# STM32WB09.net
KiCad netlist of a schematic drawn in Altium Designer
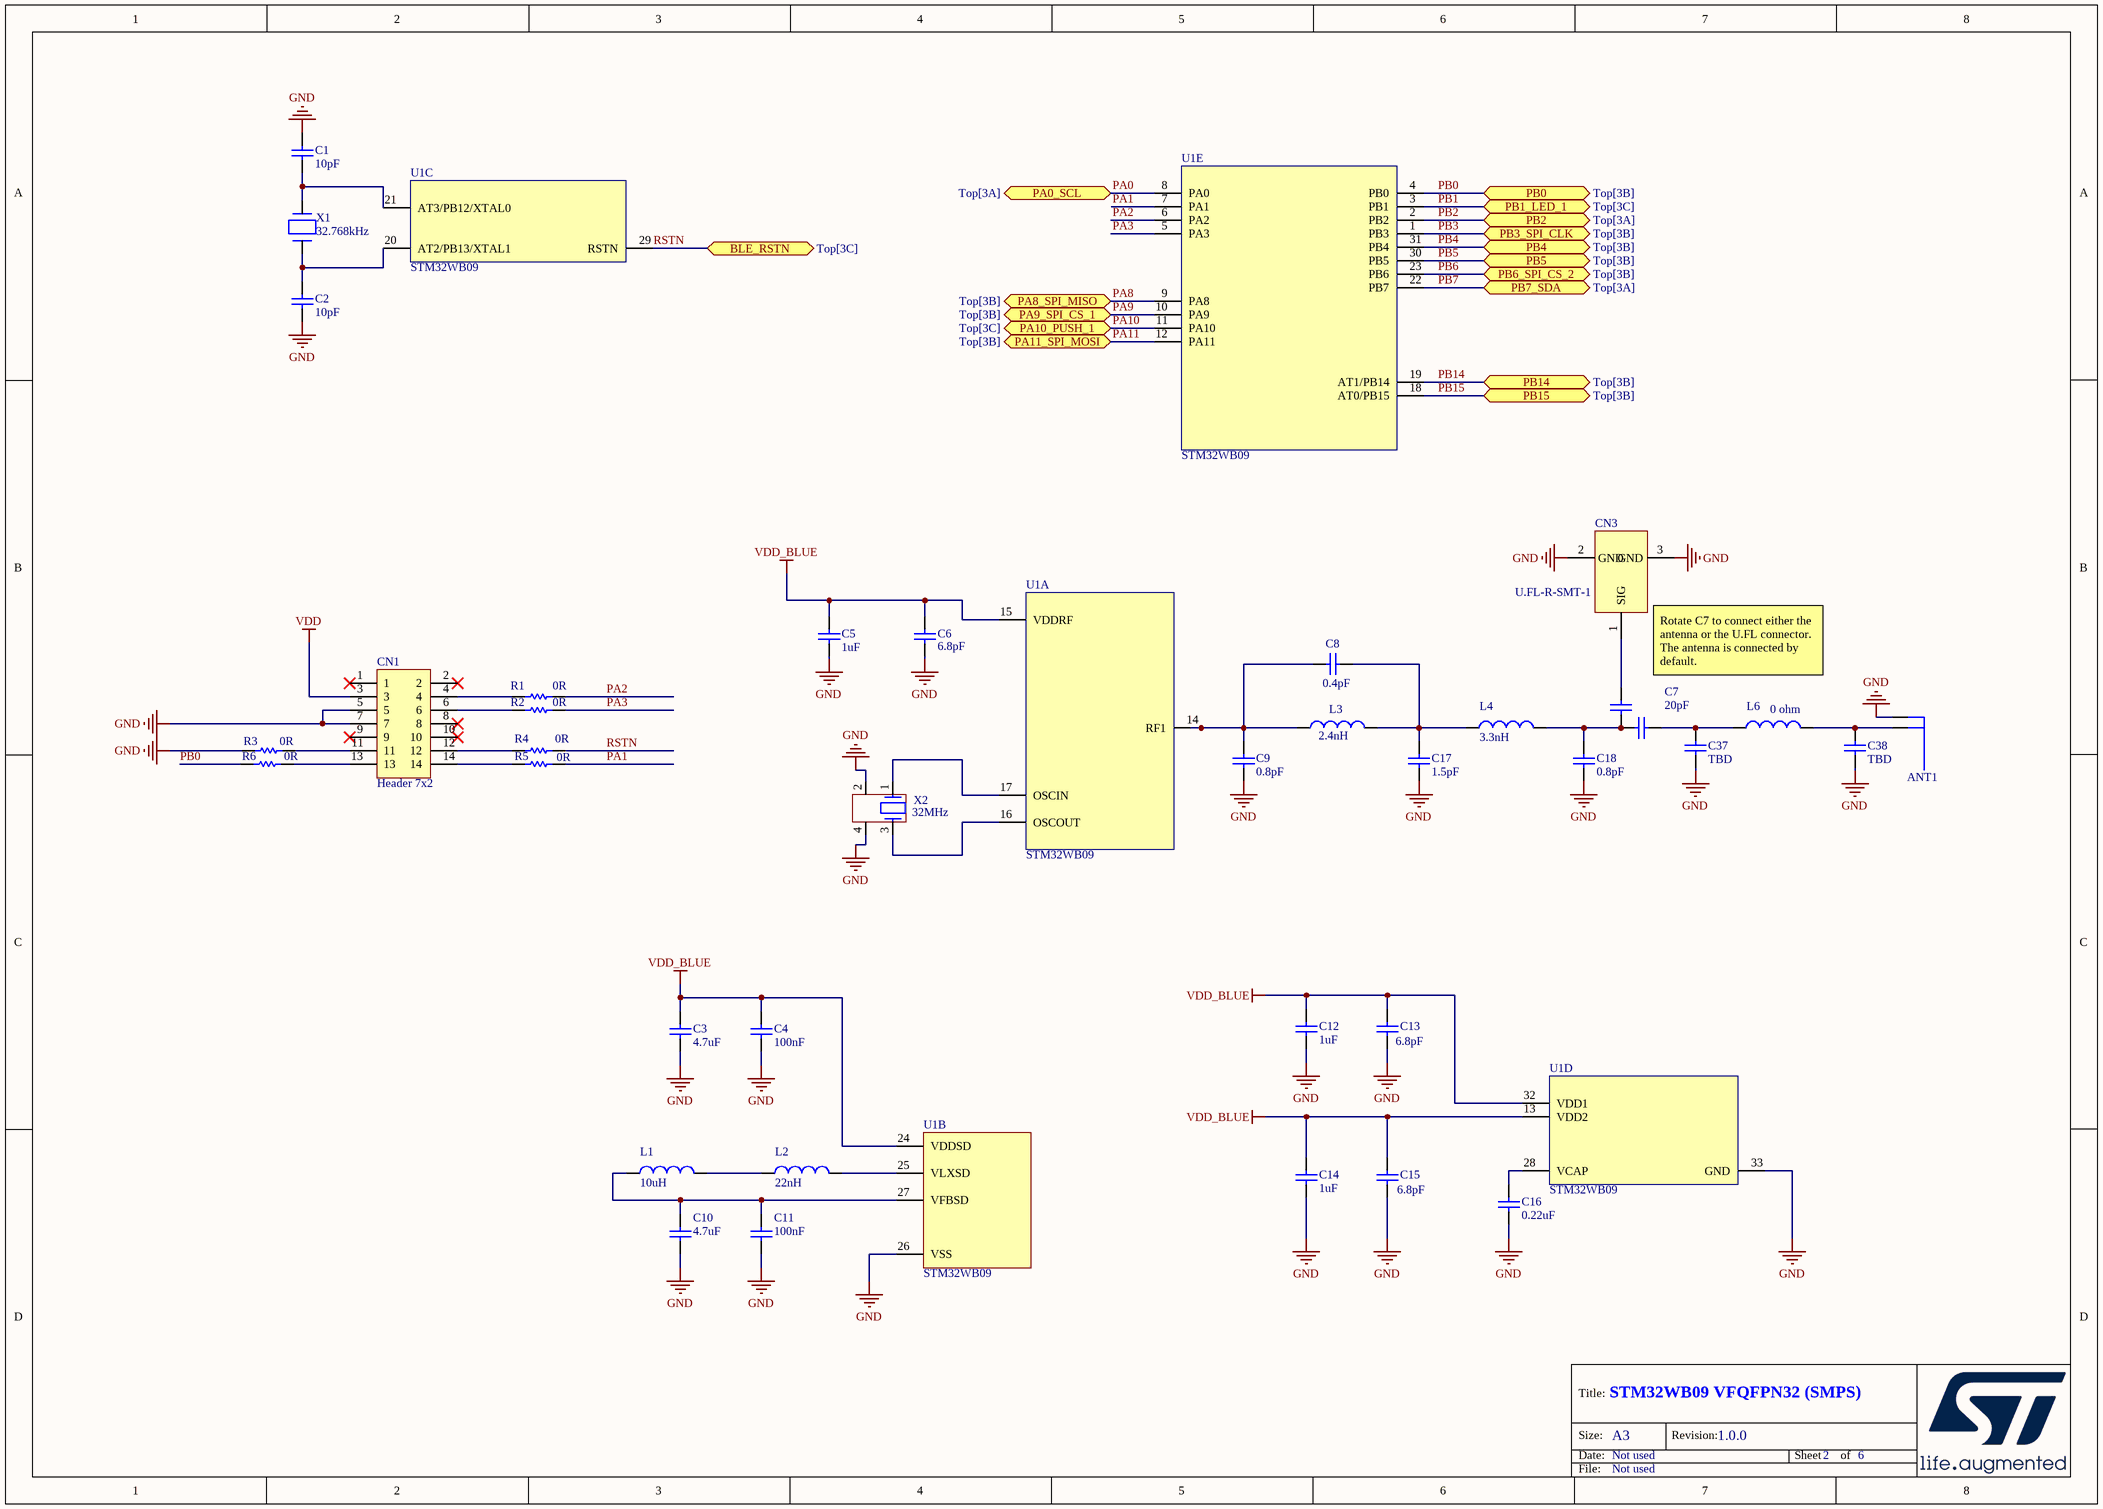
[diagram p0: STM32WB09.SchDoc]

(export (version "E")
  (design (tool "Eeschema 10.0.6"))
  (components
    (comp (ref "ANT1")
      (value "BLE_ANT")
      (footprint "ANTENNA_F")
      (description "2.4 GHz PIFA")
      (libsource (lib "STEVAL-ESLBLECB") (part "BLE_ANT"))
    )
    (comp (ref "C1")
      (value "10pF")
      (footprint "C0402")
      (description "Capacitor, MLCC, 10pF, 50V, NPO, +/-5%, 0402, T=0.5mm")
      (fields (field (name "INTERNAL_PART_NUMBER") "MCD-00015") (field (name "MANUFACTURER") "YAGEO"))
      (libsource (lib "MCD_PARTS_database") (part "Capacitor"))
    )
    (comp (ref "C2")
      (value "10pF")
      (footprint "C0402")
      (description "Capacitor, MLCC, 10pF, 50V, NPO, +/-5%, 0402, T=0.5mm")
      (fields (field (name "INTERNAL_PART_NUMBER") "MCD-00015") (field (name "MANUFACTURER") "YAGEO"))
      (libsource (lib "MCD_PARTS_database") (part "Capacitor"))
    )
    (comp (ref "C3")
      (value "4.7uF")
      (footprint "C0402")
      (description "Capacitor, MLCC, 4.7uF, X5R, 10V, +/-20%, 0402, T=0.5mm")
      (fields (field (name "INTERNAL_PART_NUMBER") "MCD-03431") (field (name "MANUFACTURER") "MURATA"))
      (libsource (lib "MCD_PARTS_database") (part "Capacitor"))
    )
    (comp (ref "C4")
      (value "100nF")
      (footprint "C0201_H0P3")
      (description "Capacitor, MLCC,100nF, 10V, X5R, +/-10%, 0201, T=0.3mm")
      (fields (field (name "INTERNAL_PART_NUMBER") "MCD-01535") (field (name "MANUFACTURER") "MURATA"))
      (libsource (lib "MCD_PARTS_database") (part "Capacitor"))
    )
    (comp (ref "C5")
      (value "1uF")
      (footprint "C0402")
      (description "Capacitor, MLCC, 1uF, X7R, 6.3V,+/- 10%, 0402, T=0.5mm")
      (fields (field (name "INTERNAL_PART_NUMBER") "MCD-03432") (field (name "MANUFACTURER") "MURATA"))
      (libsource (lib "MCD_PARTS_database") (part "Capacitor"))
    )
    (comp (ref "C6")
      (value "6.8pF")
      (footprint "C0201_H0P3")
      (description "Cap Ceramic 6.8pF 25V C0G 0.25pF SMD 0201 125°C Paper T/R")
      (fields
        (field (name "MANUFACTURER") "Murata")
        (field (name "MANUFACTURER PART NUMBER") "GJM0335C1E6R8CB01D")
      )
      (libsource (lib "MCD_PARTS_database") (part "Capacitor"))
    )
    (comp (ref "C7")
      (value "20pF")
      (footprint "SMD 0201 DEV")
      (description "Cap Ceramic 20pF 25V C0G 2% Pad SMD 0201 125C T/R")
      (fields
        (field (name "MANUFACTURER") "Murata")
        (field (name "MANUFACTURER PART NUMBER") "GJM0335C1E200GB01D")
      )
      (libsource (lib "STEVAL-ESLBLECB") (part "C_0201_DEV"))
    )
    (comp (ref "C8")
      (value "0.4pF")
      (footprint "0_5p_capacitor_SMD_0201")
      (description "0201 0.4 pF 25 V ±0.05 pF Tolerance C0G SMT Multilayer Ceramic Capacitor")
      (fields
        (field (name "MANUFACTURER") "Murata")
        (field (name "MANUFACTURER PART NUMBER") "GJM0335C1ER40WB01D")
      )
      (libsource (lib "STEVAL-ESLBLECB") (part "MCD-02284_2"))
    )
    (comp (ref "C9")
      (value "0.8pF")
      (footprint "0_8p_capacitor_SMD_0201")
      (description "Multilayer Ceramic Capacitor, 0.8 pF, 25 V, ± 0.05pF, C0G (NP0), 0201 [0603 Metric]")
      (fields
        (field (name "MANUFACTURER") "Murata")
        (field (name "MANUFACTURER PART NUMBER") "GJM0335C1ER80WB01D")
      )
      (libsource (lib "STEVAL-ESLBLECB") (part "MCD-02284_1"))
    )
    (comp (ref "C10")
      (value "4.7uF")
      (footprint "C0402")
      (description "Capacitor, MLCC, 4.7uF, X5R, 10V, +/-20%, 0402, T=0.5mm")
      (fields (field (name "INTERNAL_PART_NUMBER") "MCD-03431") (field (name "MANUFACTURER") "MURATA"))
      (libsource (lib "MCD_PARTS_database") (part "Capacitor"))
    )
    (comp (ref "C11")
      (value "100nF")
      (footprint "C0402")
      (description "Capacitor, MLCC, 100nF, +/-10%, X7R, 25V, 0402, T=0.5mm")
      (fields (field (name "INTERNAL_PART_NUMBER") "MCD-03442") (field (name "MANUFACTURER") "MURATA"))
      (libsource (lib "MCD_PARTS_database") (part "Capacitor"))
    )
    (comp (ref "C12")
      (value "1uF")
      (footprint "C0402")
      (description "Capacitor, MLCC, 1uF, X7R, 6.3V,+/- 10%, 0402, T=0.5mm")
      (fields (field (name "INTERNAL_PART_NUMBER") "MCD-03432") (field (name "MANUFACTURER") "MURATA"))
      (libsource (lib "MCD_PARTS_database") (part "Capacitor"))
    )
    (comp (ref "C13")
      (value "6.8pF")
      (footprint "C0201_H0P3")
      (description "Cap Ceramic 6.8pF 25V C0G 0.25pF SMD 0201 125°C Paper T/R")
      (fields
        (field (name "MANUFACTURER") "Murata")
        (field (name "MANUFACTURER PART NUMBER") "GJM0335C1E6R8CB01D")
      )
      (libsource (lib "MCD_PARTS_database") (part "Capacitor"))
    )
    (comp (ref "C14")
      (value "1uF")
      (footprint "C0402")
      (description "Capacitor, MLCC, 1uF, X7R, 6.3V,+/- 10%, 0402, T=0.5mm")
      (fields (field (name "INTERNAL_PART_NUMBER") "MCD-03432") (field (name "MANUFACTURER") "MURATA"))
      (libsource (lib "MCD_PARTS_database") (part "Capacitor"))
    )
    (comp (ref "C15")
      (value "6.8pF")
      (footprint "C0201_H0P3")
      (description "Cap Ceramic 6.8pF 25V C0G 0.25pF SMD 0201 125°C Paper T/R")
      (fields
        (field (name "MANUFACTURER") "Murata")
        (field (name "MANUFACTURER PART NUMBER") "GJM0335C1E6R8CB01D")
      )
      (libsource (lib "MCD_PARTS_database") (part "Capacitor"))
    )
    (comp (ref "C16")
      (value "0.22uF")
      (footprint "C0402")
      (description "Capacitor, MLCC, 0.22uF, X5R, 6.3V, +/-10%, 0402, T=0.5mm")
      (fields (field (name "INTERNAL_PART_NUMBER") "MCD-03483") (field (name "MANUFACTURER") "YAGEO"))
      (libsource (lib "MCD_PARTS_database") (part "Capacitor"))
    )
    (comp (ref "C17")
      (value "1.5pF")
      (footprint "1_5p_capacitor_SMD_0201")
      (description "Multilayer Ceramic Capacitor, 1.5 pF, 25 V, ± 0.1pF, C0G (NP0), 0201 [0603 Metric]")
      (fields
        (field (name "MANUFACTURER") "Murata")
        (field (name "MANUFACTURER PART NUMBER") "GJM0335C1E1R5BB01D")
      )
      (libsource (lib "STEVAL-ESLBLECB") (part "MCD-02284_3"))
    )
    (comp (ref "C18")
      (value "0.8pF")
      (footprint "0_8p_capacitor_SMD_0201")
      (description "Multilayer Ceramic Capacitor, 0.8 pF, 25 V, ± 0.05pF, C0G (NP0), 0201 [0603 Metric]")
      (fields
        (field (name "MANUFACTURER") "Murata")
        (field (name "MANUFACTURER PART NUMBER") "GJM0335C1ER80WB01D")
      )
      (libsource (lib "STEVAL-ESLBLECB") (part "MCD-02284_1"))
    )
    (comp (ref "C37")
      (value "TBD")
      (footprint "1_5p_capacitor_SMD_0201")
      (description "Multilayer Ceramic Capacitor, 1.5 pF, 25 V, ± 0.1pF, C0G (NP0), 0201 [0603 Metric]")
      (fields
        (field (name "MANUFACTURER") "Murata")
        (field (name "MANUFACTURER PART NUMBER") "GJM0335C1E1R5BB01D")
      )
      (libsource (lib "STEVAL-ESLBLECB") (part "MCD-02284_3"))
    )
    (comp (ref "C38")
      (value "TBD")
      (footprint "0_8p_capacitor_SMD_0201")
      (description "Multilayer Ceramic Capacitor, 0.8 pF, 25 V, ± 0.05pF, C0G (NP0), 0201 [0603 Metric]")
      (fields
        (field (name "MANUFACTURER") "Murata")
        (field (name "MANUFACTURER PART NUMBER") "GJM0335C1ER80WB01D")
      )
      (libsource (lib "STEVAL-ESLBLECB") (part "MCD-02284_1"))
    )
    (comp (ref "CN1")
      (value "Header 7x2")
      (footprint "CON_STDC14_Receiver_SMALL")
      (description "Header, 7x2, 1.27mm, VR, SMD, T=5.97mm")
      (fields (field (name "INTERNAL_PART_NUMBER") "MCD-00639") (field (name "MANUFACTURER") "SAMTEC"))
      (libsource (lib "MCD_PARTS_database") (part "Header 7x2"))
    )
    (comp (ref "CN3")
      (value "U.FL-R-SMT-1")
      (footprint "CON_HRS_U.FL-R-SMT-1")
      (description "Connector_RF, 0Hz to 6GHz, 50R, VR, SMD, T= 1.25mm")
      (fields (field (name "INTERNAL_PART_NUMBER") "MCD-01583") (field (name "BMS_PART_NUMBER") "9187005"))
      (libsource (lib "STEVAL-ESLBLECB") (part "MCD-01583"))
    )
    (comp (ref "L1")
      (value "10uH")
      (footprint "IND_0805_MURATA_LQM21")
      (description "Inductor, MLCC, 10uH, +/-20%, 300mA, 845mR, 0805, T=1.45mm")
      (fields (field (name "INTERNAL_PART_NUMBER") "MCD-03438") (field (name "MANUFACTURER") "MURATA"))
      (libsource (lib "MCD_PARTS_database") (part "Inductor"))
    )
    (comp (ref "L2")
      (value "22nH")
      (footprint "C0402")
      (description "Inductor, MLCC, 22nH, +/-2%, 350mA, 0.58R, 0402, T=1.45mm")
      (fields (field (name "INTERNAL_PART_NUMBER") "MCD-03439") (field (name "MANUFACTURER") "MURATA"))
      (libsource (lib "MCD_PARTS_database") (part "Inductor"))
    )
    (comp (ref "L3")
      (value "2.4nH")
      (footprint "2n4_inductor_SMD_0201")
      (description "Inductor RF Chip Thin Film 2.4nH 0.1nH 500MHz 14Q-Factor 500mA 200mOhm DCR 0201 Paper T/R")
      (fields
        (field (name "MANUFACTURER") "Murata")
        (field (name "MANUFACTURER PART NUMBER") "LQP03TN2N4B02D")
      )
      (libsource (lib "STEVAL-ESLBLECB") (part "MCD-03552"))
    )
    (comp (ref "L4")
      (value "3.3nH")
      (footprint "3n3_inductor_SMD_0201")
      (description "Inductor RF Chip Thin Film 3.3nH 0.1nH 500MHz 14Q-Factor 450mA 250mOhm DCR 0201 Paper T/R")
      (fields
        (field (name "MANUFACTURER") "Murata")
        (field (name "MANUFACTURER PART NUMBER") "LQP03TN3N3B02D")
      )
      (libsource (lib "STEVAL-ESLBLECB") (part "MCD-03552_1"))
    )
    (comp (ref "L6")
      (value "0 ohm")
      (footprint "3n3_inductor_SMD_0201")
      (description "0201 0 ohm")
      (fields (field (name "Comment") "Inductor"))
      (libsource (lib "STEVAL-ESLBLECB") (part "MCD-03552_1"))
    )
    (comp (ref "R1")
      (value "0R")
      (footprint "R0402")
      (description "Resistor, 0R, 0402, +/-5%, 1/16W")
      (fields (field (name "INTERNAL_PART_NUMBER") "MCD-00052") (field (name "MANUFACTURER") "YAGEO"))
      (libsource (lib "MCD_PARTS_database") (part "Resistor"))
    )
    (comp (ref "R2")
      (value "0R")
      (footprint "R0402")
      (description "Resistor, 0R, 0402, +/-5%, 1/16W")
      (fields (field (name "INTERNAL_PART_NUMBER") "MCD-00052") (field (name "MANUFACTURER") "YAGEO"))
      (libsource (lib "MCD_PARTS_database") (part "Resistor"))
    )
    (comp (ref "R3")
      (value "0R")
      (footprint "R0402")
      (description "Resistor, 0R, 0402, +/-5%, 1/16W")
      (fields (field (name "INTERNAL_PART_NUMBER") "MCD-00052") (field (name "MANUFACTURER") "YAGEO"))
      (libsource (lib "MCD_PARTS_database") (part "Resistor"))
    )
    (comp (ref "R4")
      (value "0R")
      (footprint "R0402")
      (description "Resistor, 0R, 0402, +/-5%, 1/16W")
      (fields (field (name "INTERNAL_PART_NUMBER") "MCD-00052") (field (name "MANUFACTURER") "YAGEO"))
      (libsource (lib "MCD_PARTS_database") (part "Resistor"))
    )
    (comp (ref "R5")
      (value "0R")
      (footprint "R0402")
      (description "Resistor, 0R, 0402, +/-5%, 1/16W")
      (fields (field (name "INTERNAL_PART_NUMBER") "MCD-00052") (field (name "MANUFACTURER") "YAGEO"))
      (libsource (lib "MCD_PARTS_database") (part "Resistor"))
    )
    (comp (ref "R6")
      (value "0R")
      (footprint "R0402")
      (description "Resistor, 0R, 0402, +/-5%, 1/16W")
      (fields (field (name "INTERNAL_PART_NUMBER") "MCD-00052") (field (name "MANUFACTURER") "YAGEO"))
      (libsource (lib "MCD_PARTS_database") (part "Resistor"))
    )
    (comp (ref "U1")
      (value "STM32WB09")
      (footprint "ICC_QFN32-EPAD_5X5_P050")
      (description "Bluetooth® Low Energy wireless SoC")
      (fields
        (field (name "INTERNAL_PART_NUMBER") "MCD-03444")
        (field (name "MANUFACTURER") "STMICROELECTRONICS")
      )
      (libsource (lib "MCD_PARTS_database") (part "STM32WB09"))
    )
    (comp (ref "X1")
      (value "32.768kHz")
      (footprint "CRY_NX2012SA_2P")
      (description "Crystal, 32.768kHz, 7pF, +/-20ppm, 80K, 2.05x1.2mm")
      (fields (field (name "INTERNAL_PART_NUMBER") "MCD-01445") (field (name "BMS_PART_NUMBER") "9157043"))
      (libsource (lib "MCD_PARTS_database") (part "XTAL_2_PINS"))
    )
    (comp (ref "X2")
      (value "32MHz")
      (footprint "CRY_NX2016SA_4P")
      (description "Crystal, 32MHz, 8pF, +/-10ppm, 60R, 2x1.6mm")
      (fields (field (name "INTERNAL_PART_NUMBER") "MCD-01446") (field (name "BMS_PART_NUMBER") "9157042"))
      (libsource (lib "MCD_PARTS_database") (part "XTAL_4_PINS"))
    )
  )
  (nets
    (net (code "1") (name "/PA0") (class "Default")
      (node (ref "U1") (pin "8") (pinfunction "PA0_8") (pintype "passive"))
    )
    (net (code "2") (name "/PA1") (class "Default")
      (node (ref "R5") (pin "2") (pinfunction "2_2") (pintype "passive"))
      (node (ref "U1") (pin "7") (pinfunction "PA1_7") (pintype "passive"))
    )
    (net (code "3") (name "/PA2") (class "Default")
      (node (ref "R1") (pin "2") (pinfunction "2_2") (pintype "passive"))
      (node (ref "U1") (pin "6") (pinfunction "PA2_6") (pintype "passive"))
    )
    (net (code "4") (name "/PA3") (class "Default")
      (node (ref "R2") (pin "2") (pinfunction "2_2") (pintype "passive"))
      (node (ref "U1") (pin "5") (pinfunction "PA3_5") (pintype "passive"))
    )
    (net (code "5") (name "/PA8") (class "Default")
      (node (ref "U1") (pin "9") (pinfunction "PA8_9") (pintype "passive"))
    )
    (net (code "6") (name "/PA9") (class "Default")
      (node (ref "U1") (pin "10") (pinfunction "PA9_10") (pintype "passive"))
    )
    (net (code "7") (name "/PA10") (class "Default")
      (node (ref "U1") (pin "11") (pinfunction "PA10_11") (pintype "passive"))
    )
    (net (code "8") (name "/PA11") (class "Default")
      (node (ref "U1") (pin "12") (pinfunction "PA11_12") (pintype "passive"))
    )
    (net (code "9") (name "/PB0") (class "Default")
      (node (ref "R6") (pin "1") (pinfunction "1_1") (pintype "passive"))
      (node (ref "U1") (pin "4") (pinfunction "PB0_4") (pintype "passive"))
    )
    (net (code "10") (name "/PB1") (class "Default")
      (node (ref "U1") (pin "3") (pinfunction "PB1_3") (pintype "passive"))
    )
    (net (code "11") (name "/PB2") (class "Default")
      (node (ref "U1") (pin "2") (pinfunction "PB2_2") (pintype "passive"))
    )
    (net (code "12") (name "/PB3") (class "Default")
      (node (ref "U1") (pin "1") (pinfunction "PB3_1") (pintype "passive"))
    )
    (net (code "13") (name "/PB4") (class "Default")
      (node (ref "U1") (pin "31") (pinfunction "PB4_31") (pintype "passive"))
    )
    (net (code "14") (name "/PB5") (class "Default")
      (node (ref "U1") (pin "30") (pinfunction "PB5_30") (pintype "passive"))
    )
    (net (code "15") (name "/PB6") (class "Default")
      (node (ref "U1") (pin "23") (pinfunction "PB6_23") (pintype "passive"))
    )
    (net (code "16") (name "/PB7") (class "Default")
      (node (ref "U1") (pin "22") (pinfunction "PB7_22") (pintype "passive"))
    )
    (net (code "17") (name "/PB14") (class "Default")
      (node (ref "U1") (pin "19") (pinfunction "AT1/PB14_19") (pintype "passive"))
    )
    (net (code "18") (name "/PB15") (class "Default")
      (node (ref "U1") (pin "18") (pinfunction "AT0/PB15_18") (pintype "passive"))
    )
    (net (code "19") (name "/RSTN") (class "Default")
      (node (ref "R4") (pin "2") (pinfunction "2_2") (pintype "passive"))
      (node (ref "U1") (pin "29") (pinfunction "RSTN_29") (pintype "passive"))
    )
    (net (code "20") (name "GND") (class "Default")
      (node (ref "ANT1") (pin "2") (pinfunction "2_2") (pintype "passive"))
      (node (ref "C1") (pin "2") (pinfunction "2_2") (pintype "passive"))
      (node (ref "C10") (pin "1") (pinfunction "1_1") (pintype "passive"))
      (node (ref "C11") (pin "1") (pinfunction "1_1") (pintype "passive"))
      (node (ref "C12") (pin "1") (pinfunction "1_1") (pintype "passive"))
      (node (ref "C13") (pin "1") (pinfunction "1_1") (pintype "passive"))
      (node (ref "C14") (pin "1") (pinfunction "1_1") (pintype "passive"))
      (node (ref "C15") (pin "1") (pinfunction "1_1") (pintype "passive"))
      (node (ref "C16") (pin "1") (pinfunction "1_1") (pintype "passive"))
      (node (ref "C17") (pin "1") (pinfunction "1_1") (pintype "passive"))
      (node (ref "C18") (pin "1") (pinfunction "1_1") (pintype "passive"))
      (node (ref "C2") (pin "1") (pinfunction "1_1") (pintype "passive"))
      (node (ref "C3") (pin "1") (pinfunction "1_1") (pintype "passive"))
      (node (ref "C37") (pin "1") (pinfunction "1_1") (pintype "passive"))
      (node (ref "C38") (pin "1") (pinfunction "1_1") (pintype "passive"))
      (node (ref "C4") (pin "1") (pinfunction "1_1") (pintype "passive"))
      (node (ref "C5") (pin "1") (pinfunction "1_1") (pintype "passive"))
      (node (ref "C6") (pin "1") (pinfunction "1_1") (pintype "passive"))
      (node (ref "C9") (pin "1") (pinfunction "1_1") (pintype "passive"))
      (node (ref "CN1") (pin "5") (pinfunction "5_5") (pintype "passive"))
      (node (ref "CN1") (pin "7") (pinfunction "7_7") (pintype "passive"))
      (node (ref "CN3") (pin "2") (pinfunction "GND_2") (pintype "passive"))
      (node (ref "CN3") (pin "3") (pinfunction "GND_3") (pintype "passive"))
      (node (ref "R3") (pin "1") (pinfunction "1_1") (pintype "passive"))
      (node (ref "U1") (pin "26") (pinfunction "VSS_26") (pintype "passive"))
      (node (ref "U1") (pin "33") (pinfunction "GND_33") (pintype "passive"))
      (node (ref "X2") (pin "2") (pinfunction "2_2") (pintype "passive"))
      (node (ref "X2") (pin "4") (pinfunction "4_4") (pintype "passive"))
    )
    (net (code "21") (name "Net-(ANT1-Pad1)") (class "Default")
      (node (ref "ANT1") (pin "1") (pinfunction "1_1") (pintype "passive"))
      (node (ref "C38") (pin "2") (pinfunction "2_2") (pintype "passive"))
      (node (ref "L6") (pin "2") (pinfunction "2_2") (pintype "passive"))
    )
    (net (code "22") (name "Net-(C17-Pad2)") (class "Default")
      (node (ref "C17") (pin "2") (pinfunction "2_2") (pintype "passive"))
      (node (ref "C8") (pin "2") (pinfunction "2_2") (pintype "passive"))
      (node (ref "L3") (pin "2") (pinfunction "2_2") (pintype "passive"))
      (node (ref "L4") (pin "1") (pinfunction "1_1") (pintype "passive"))
    )
    (net (code "23") (name "Net-(C18-Pad2)") (class "Default")
      (node (ref "C18") (pin "2") (pinfunction "2_2") (pintype "passive"))
      (node (ref "C7") (pin "1") (pinfunction "1_1") (pintype "passive"))
      (node (ref "L4") (pin "2") (pinfunction "2_2") (pintype "passive"))
    )
    (net (code "24") (name "Net-(C37-Pad2)") (class "Default")
      (node (ref "C37") (pin "2") (pinfunction "2_2") (pintype "passive"))
      (node (ref "C7") (pin "3") (pinfunction "3_3") (pintype "passive"))
      (node (ref "L6") (pin "1") (pinfunction "1_1") (pintype "passive"))
    )
    (net (code "25") (name "Net-(CN1-Pad4)") (class "Default")
      (node (ref "CN1") (pin "4") (pinfunction "4_4") (pintype "passive"))
      (node (ref "R1") (pin "1") (pinfunction "1_1") (pintype "passive"))
    )
    (net (code "26") (name "Net-(CN1-Pad6)") (class "Default")
      (node (ref "CN1") (pin "6") (pinfunction "6_6") (pintype "passive"))
      (node (ref "R2") (pin "1") (pinfunction "1_1") (pintype "passive"))
    )
    (net (code "27") (name "Net-(CN1-Pad11)") (class "Default")
      (node (ref "CN1") (pin "11") (pinfunction "11_11") (pintype "passive"))
      (node (ref "R3") (pin "2") (pinfunction "2_2") (pintype "passive"))
    )
    (net (code "28") (name "Net-(CN1-Pad12)") (class "Default")
      (node (ref "CN1") (pin "12") (pinfunction "12_12") (pintype "passive"))
      (node (ref "R4") (pin "1") (pinfunction "1_1") (pintype "passive"))
    )
    (net (code "29") (name "Net-(CN1-Pad13)") (class "Default")
      (node (ref "CN1") (pin "13") (pinfunction "13_13") (pintype "passive"))
      (node (ref "R6") (pin "2") (pinfunction "2_2") (pintype "passive"))
    )
    (net (code "30") (name "Net-(CN1-Pad14)") (class "Default")
      (node (ref "CN1") (pin "14") (pinfunction "14_14") (pintype "passive"))
      (node (ref "R5") (pin "1") (pinfunction "1_1") (pintype "passive"))
    )
    (net (code "31") (name "Net-(CN3-SIG)") (class "Default")
      (node (ref "C7") (pin "2") (pinfunction "2_2") (pintype "passive"))
      (node (ref "CN3") (pin "1") (pinfunction "SIG_1") (pintype "passive"))
    )
    (net (code "32") (name "Net-(L1-Pad2)") (class "Default")
      (node (ref "L1") (pin "2") (pinfunction "2_2") (pintype "passive"))
      (node (ref "L2") (pin "1") (pinfunction "1_1") (pintype "passive"))
    )
    (net (code "33") (name "Net-(U1A-OSCIN)") (class "Default")
      (node (ref "U1") (pin "17") (pinfunction "OSCIN_17") (pintype "passive"))
      (node (ref "X2") (pin "1") (pinfunction "1_1") (pintype "passive"))
    )
    (net (code "34") (name "Net-(U1A-OSCOUT)") (class "Default")
      (node (ref "U1") (pin "16") (pinfunction "OSCOUT_16") (pintype "passive"))
      (node (ref "X2") (pin "3") (pinfunction "3_3") (pintype "passive"))
    )
    (net (code "35") (name "Net-(U1A-RF1)") (class "Default")
      (node (ref "C8") (pin "1") (pinfunction "1_1") (pintype "passive"))
      (node (ref "C9") (pin "2") (pinfunction "2_2") (pintype "passive"))
      (node (ref "L3") (pin "1") (pinfunction "1_1") (pintype "passive"))
      (node (ref "U1") (pin "14") (pinfunction "RF1_14") (pintype "passive"))
    )
    (net (code "36") (name "Net-(U1B-VFBSD)") (class "Default")
      (node (ref "C10") (pin "2") (pinfunction "2_2") (pintype "passive"))
      (node (ref "C11") (pin "2") (pinfunction "2_2") (pintype "passive"))
      (node (ref "L1") (pin "1") (pinfunction "1_1") (pintype "passive"))
      (node (ref "U1") (pin "27") (pinfunction "VFBSD_27") (pintype "passive"))
    )
    (net (code "37") (name "Net-(U1B-VLXSD)") (class "Default")
      (node (ref "L2") (pin "2") (pinfunction "2_2") (pintype "passive"))
      (node (ref "U1") (pin "25") (pinfunction "VLXSD_25") (pintype "passive"))
    )
    (net (code "38") (name "Net-(U1C-AT2{slash}PB13{slash}XTAL1)") (class "Default")
      (node (ref "C2") (pin "2") (pinfunction "2_2") (pintype "passive"))
      (node (ref "U1") (pin "20") (pinfunction "AT2/PB13/XTAL1_20") (pintype "passive"))
      (node (ref "X1") (pin "2") (pinfunction "X2_2") (pintype "passive"))
    )
    (net (code "39") (name "Net-(U1C-AT3{slash}PB12{slash}XTAL0)") (class "Default")
      (node (ref "C1") (pin "1") (pinfunction "1_1") (pintype "passive"))
      (node (ref "U1") (pin "21") (pinfunction "AT3/PB12/XTAL0_21") (pintype "passive"))
      (node (ref "X1") (pin "1") (pinfunction "X1_1") (pintype "passive"))
    )
    (net (code "40") (name "Net-(U1D-VCAP)") (class "Default")
      (node (ref "C16") (pin "2") (pinfunction "2_2") (pintype "passive"))
      (node (ref "U1") (pin "28") (pinfunction "VCAP_28") (pintype "passive"))
    )
    (net (code "41") (name "VDD") (class "Default")
      (node (ref "CN1") (pin "3") (pinfunction "3_3") (pintype "passive"))
    )
    (net (code "42") (name "VDD_BLUE") (class "Default")
      (node (ref "C12") (pin "2") (pinfunction "2_2") (pintype "passive"))
      (node (ref "C13") (pin "2") (pinfunction "2_2") (pintype "passive"))
      (node (ref "C14") (pin "2") (pinfunction "2_2") (pintype "passive"))
      (node (ref "C15") (pin "2") (pinfunction "2_2") (pintype "passive"))
      (node (ref "C3") (pin "2") (pinfunction "2_2") (pintype "passive"))
      (node (ref "C4") (pin "2") (pinfunction "2_2") (pintype "passive"))
      (node (ref "C5") (pin "2") (pinfunction "2_2") (pintype "passive"))
      (node (ref "C6") (pin "2") (pinfunction "2_2") (pintype "passive"))
      (node (ref "U1") (pin "13") (pinfunction "VDD2_13") (pintype "passive"))
      (node (ref "U1") (pin "15") (pinfunction "VDDRF_15") (pintype "passive"))
      (node (ref "U1") (pin "24") (pinfunction "VDDSD_24") (pintype "passive"))
      (node (ref "U1") (pin "32") (pinfunction "VDD1_32") (pintype "passive"))
    )
    (net (code "43") (name "unconnected-(CN1-Pad1)") (class "Default")
      (node (ref "CN1") (pin "1") (pinfunction "1_1") (pintype "passive+no_connect"))
    )
    (net (code "44") (name "unconnected-(CN1-Pad2)") (class "Default")
      (node (ref "CN1") (pin "2") (pinfunction "2_2") (pintype "passive+no_connect"))
    )
    (net (code "45") (name "unconnected-(CN1-Pad8)") (class "Default")
      (node (ref "CN1") (pin "8") (pinfunction "8_8") (pintype "passive+no_connect"))
    )
    (net (code "46") (name "unconnected-(CN1-Pad9)") (class "Default")
      (node (ref "CN1") (pin "9") (pinfunction "9_9") (pintype "passive+no_connect"))
    )
    (net (code "47") (name "unconnected-(CN1-Pad10)") (class "Default")
      (node (ref "CN1") (pin "10") (pinfunction "10_10") (pintype "passive+no_connect"))
    )
  )
)
